# Analog_readout.net
KiCad netlist of a schematic drawn in Altium Designer
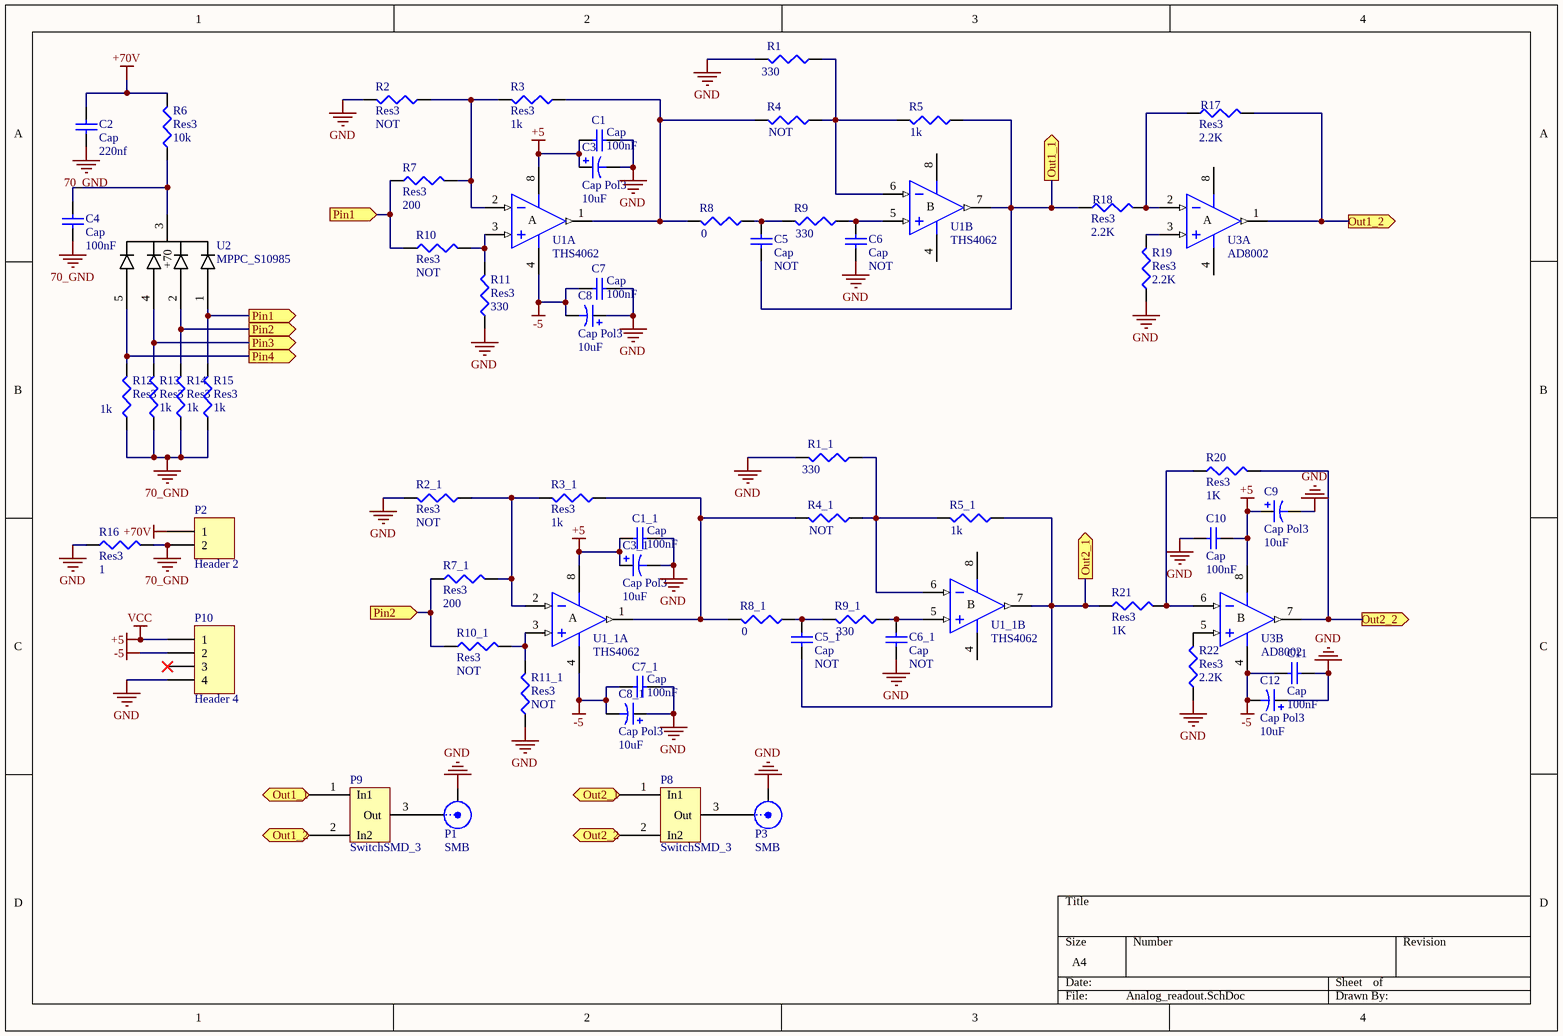
[diagram p0: Analog_readout.SchDoc]

(export (version "E")
  (design (tool "Eeschema 10.0.6"))
  (components
    (comp (ref "C1")
      (value "Cap")
      (footprint "6-0805_N")
      (description "Capacitor")
      (fields (field (name "ALTIUM_VALUE") "100nF") (field (name "PUBLISHER") "Altium Limited"))
      (libsource (lib "Miscellaneous Devices") (part "Cap"))
    )
    (comp (ref "C1_1")
      (value "Cap")
      (footprint "6-0805_N")
      (description "Capacitor")
      (fields (field (name "ALTIUM_VALUE") "100nF") (field (name "PUBLISHER") "Altium Limited"))
      (libsource (lib "Miscellaneous Devices") (part "Cap"))
    )
    (comp (ref "C2")
      (value "Cap")
      (footprint "6-0805_N")
      (description "Capacitor")
      (fields (field (name "ALTIUM_VALUE") "220nf") (field (name "PUBLISHER") "Altium Limited"))
      (libsource (lib "Miscellaneous Devices") (part "Cap"))
    )
    (comp (ref "C3")
      (value "Cap Pol3")
      (footprint "6-0805_N")
      (description "Polarized Capacitor (Surface Mount)")
      (fields (field (name "ALTIUM_VALUE") "10uF") (field (name "PUBLISHER") "Altium Limited"))
      (libsource (lib "Miscellaneous Devices") (part "Cap Pol3"))
    )
    (comp (ref "C3_1")
      (value "Cap Pol3")
      (footprint "6-0805_N")
      (description "Polarized Capacitor (Surface Mount)")
      (fields (field (name "ALTIUM_VALUE") "10uF") (field (name "PUBLISHER") "Altium Limited"))
      (libsource (lib "Miscellaneous Devices") (part "Cap Pol3"))
    )
    (comp (ref "C4")
      (value "Cap")
      (footprint "6-0805_N")
      (description "Capacitor")
      (fields (field (name "ALTIUM_VALUE") "100nF") (field (name "PUBLISHER") "Altium Limited"))
      (libsource (lib "Miscellaneous Devices") (part "Cap"))
    )
    (comp (ref "C5")
      (value "Cap")
      (footprint "6-0805_N")
      (description "Capacitor")
      (fields (field (name "ALTIUM_VALUE") "NOT") (field (name "PUBLISHER") "Altium Limited"))
      (libsource (lib "Miscellaneous Devices") (part "Cap"))
    )
    (comp (ref "C5_1")
      (value "Cap")
      (footprint "6-0805_N")
      (description "Capacitor")
      (fields (field (name "ALTIUM_VALUE") "NOT") (field (name "PUBLISHER") "Altium Limited"))
      (libsource (lib "Miscellaneous Devices") (part "Cap"))
    )
    (comp (ref "C6")
      (value "Cap")
      (footprint "6-0805_N")
      (description "Capacitor")
      (fields (field (name "ALTIUM_VALUE") "NOT") (field (name "PUBLISHER") "Altium Limited"))
      (libsource (lib "Miscellaneous Devices") (part "Cap"))
    )
    (comp (ref "C6_1")
      (value "Cap")
      (footprint "6-0805_N")
      (description "Capacitor")
      (fields (field (name "ALTIUM_VALUE") "NOT") (field (name "PUBLISHER") "Altium Limited"))
      (libsource (lib "Miscellaneous Devices") (part "Cap"))
    )
    (comp (ref "C7")
      (value "Cap")
      (footprint "6-0805_N")
      (description "Capacitor")
      (fields (field (name "ALTIUM_VALUE") "100nF") (field (name "PUBLISHER") "Altium Limited"))
      (libsource (lib "Miscellaneous Devices") (part "Cap"))
    )
    (comp (ref "C7_1")
      (value "Cap")
      (footprint "6-0805_N")
      (description "Capacitor")
      (fields (field (name "ALTIUM_VALUE") "100nF") (field (name "PUBLISHER") "Altium Limited"))
      (libsource (lib "Miscellaneous Devices") (part "Cap"))
    )
    (comp (ref "C8")
      (value "Cap Pol3")
      (footprint "6-0805_N")
      (description "Polarized Capacitor (Surface Mount)")
      (fields (field (name "ALTIUM_VALUE") "10uF") (field (name "PUBLISHER") "Altium Limited"))
      (libsource (lib "Miscellaneous Devices") (part "Cap Pol3"))
    )
    (comp (ref "C8_1")
      (value "Cap Pol3")
      (footprint "6-0805_N")
      (description "Polarized Capacitor (Surface Mount)")
      (fields (field (name "ALTIUM_VALUE") "10uF") (field (name "PUBLISHER") "Altium Limited"))
      (libsource (lib "Miscellaneous Devices") (part "Cap Pol3"))
    )
    (comp (ref "C9")
      (value "Cap Pol3")
      (footprint "6-0805_N")
      (description "Polarized Capacitor (Surface Mount)")
      (fields (field (name "ALTIUM_VALUE") "10uF") (field (name "PUBLISHER") "Altium Limited"))
      (libsource (lib "Miscellaneous Devices") (part "Cap Pol3"))
    )
    (comp (ref "C10")
      (value "Cap")
      (footprint "6-0805_N")
      (description "Capacitor")
      (fields (field (name "ALTIUM_VALUE") "100nF") (field (name "PUBLISHER") "Altium Limited"))
      (libsource (lib "Miscellaneous Devices") (part "Cap"))
    )
    (comp (ref "C11")
      (value "Cap")
      (footprint "6-0805_N")
      (description "Capacitor")
      (fields (field (name "ALTIUM_VALUE") "100nF") (field (name "PUBLISHER") "Altium Limited"))
      (libsource (lib "Miscellaneous Devices") (part "Cap"))
    )
    (comp (ref "C12")
      (value "Cap Pol3")
      (footprint "6-0805_N")
      (description "Polarized Capacitor (Surface Mount)")
      (fields (field (name "ALTIUM_VALUE") "10uF") (field (name "PUBLISHER") "Altium Limited"))
      (libsource (lib "Miscellaneous Devices") (part "Cap Pol3"))
    )
    (comp (ref "P1")
      (value "SMB")
      (footprint "SMB_V-RJ45")
      (description "SMB Straight Connector")
      (fields (field (name "PUBLISHER") "Altium Limited"))
      (libsource (lib "Miscellaneous Connectors") (part "SMB"))
    )
    (comp (ref "P2")
      (value "Header 2")
      (footprint "HDR1X2")
      (description "Header, 2-Pin")
      (fields (field (name "PUBLISHER") "Altium Limited"))
      (libsource (lib "Miscellaneous Connectors") (part "Header 2"))
    )
    (comp (ref "P3")
      (value "SMB")
      (footprint "SMB_V-RJ45")
      (description "SMB Straight Connector")
      (fields (field (name "PUBLISHER") "Altium Limited"))
      (libsource (lib "Miscellaneous Connectors") (part "SMB"))
    )
    (comp (ref "P8")
      (value "SwitchSMD_3")
      (footprint "SwitchSMD_0603")
      (libsource (lib "Int_Lib1") (part "SwitchSMD_3"))
    )
    (comp (ref "P9")
      (value "SwitchSMD_3")
      (footprint "SwitchSMD_0603")
      (libsource (lib "Int_Lib1") (part "SwitchSMD_3"))
    )
    (comp (ref "P10")
      (value "Header 4")
      (footprint "HDR1X4")
      (description "Header, 4-Pin")
      (fields (field (name "PUBLISHER") "Altium Limited"))
      (libsource (lib "Miscellaneous Connectors") (part "Header 4"))
    )
    (comp (ref "R1")
      (value "330")
      (footprint "6-0805_N")
      (description "Resistor")
      (fields (field (name "Comment") "Res3") (field (name "PUBLISHER") "Altium Limited"))
      (libsource (lib "Miscellaneous Devices") (part "Res3"))
    )
    (comp (ref "R1_1")
      (value "330")
      (footprint "6-0805_N")
      (description "Resistor")
      (fields (field (name "Comment") "Res3") (field (name "PUBLISHER") "Altium Limited"))
      (libsource (lib "Miscellaneous Devices") (part "Res3"))
    )
    (comp (ref "R2")
      (value "Res3")
      (footprint "6-0805_N")
      (description "Resistor")
      (fields (field (name "ALTIUM_VALUE") "NOT") (field (name "PUBLISHER") "Altium Limited"))
      (libsource (lib "Miscellaneous Devices") (part "Res3"))
    )
    (comp (ref "R2_1")
      (value "Res3")
      (footprint "6-0805_N")
      (description "Resistor")
      (fields (field (name "ALTIUM_VALUE") "NOT") (field (name "PUBLISHER") "Altium Limited"))
      (libsource (lib "Miscellaneous Devices") (part "Res3"))
    )
    (comp (ref "R3")
      (value "Res3")
      (footprint "6-0805_N")
      (description "Resistor")
      (fields (field (name "ALTIUM_VALUE") "1k") (field (name "PUBLISHER") "Altium Limited"))
      (libsource (lib "Miscellaneous Devices") (part "Res3"))
    )
    (comp (ref "R3_1")
      (value "Res3")
      (footprint "6-0805_N")
      (description "Resistor")
      (fields (field (name "ALTIUM_VALUE") "1k") (field (name "PUBLISHER") "Altium Limited"))
      (libsource (lib "Miscellaneous Devices") (part "Res3"))
    )
    (comp (ref "R4")
      (value "NOT")
      (footprint "6-0805_N")
      (description "Resistor")
      (fields (field (name "Comment") "Res3") (field (name "PUBLISHER") "Altium Limited"))
      (libsource (lib "Miscellaneous Devices") (part "Res3"))
    )
    (comp (ref "R4_1")
      (value "NOT")
      (footprint "6-0805_N")
      (description "Resistor")
      (fields (field (name "Comment") "Res3") (field (name "PUBLISHER") "Altium Limited"))
      (libsource (lib "Miscellaneous Devices") (part "Res3"))
    )
    (comp (ref "R5")
      (value "1k")
      (footprint "6-0805_N")
      (description "Resistor")
      (fields (field (name "Comment") "Res3") (field (name "PUBLISHER") "Altium Limited"))
      (libsource (lib "Miscellaneous Devices") (part "Res3"))
    )
    (comp (ref "R5_1")
      (value "1k")
      (footprint "6-0805_N")
      (description "Resistor")
      (fields (field (name "Comment") "Res3") (field (name "PUBLISHER") "Altium Limited"))
      (libsource (lib "Miscellaneous Devices") (part "Res3"))
    )
    (comp (ref "R6")
      (value "Res3")
      (footprint "6-0805_N")
      (description "Resistor")
      (fields (field (name "ALTIUM_VALUE") "10k") (field (name "PUBLISHER") "Altium Limited"))
      (libsource (lib "Miscellaneous Devices") (part "Res3"))
    )
    (comp (ref "R7")
      (value "Res3")
      (footprint "6-0805_N")
      (description "Resistor")
      (fields (field (name "ALTIUM_VALUE") "200") (field (name "PUBLISHER") "Altium Limited"))
      (libsource (lib "Miscellaneous Devices") (part "Res3"))
    )
    (comp (ref "R7_1")
      (value "Res3")
      (footprint "6-0805_N")
      (description "Resistor")
      (fields (field (name "ALTIUM_VALUE") "200") (field (name "PUBLISHER") "Altium Limited"))
      (libsource (lib "Miscellaneous Devices") (part "Res3"))
    )
    (comp (ref "R8")
      (value "0")
      (footprint "6-0805_N")
      (description "Resistor")
      (fields (field (name "Comment") "Res3") (field (name "PUBLISHER") "Altium Limited"))
      (libsource (lib "Miscellaneous Devices") (part "Res3"))
    )
    (comp (ref "R8_1")
      (value "0")
      (footprint "6-0805_N")
      (description "Resistor")
      (fields (field (name "Comment") "Res3") (field (name "PUBLISHER") "Altium Limited"))
      (libsource (lib "Miscellaneous Devices") (part "Res3"))
    )
    (comp (ref "R9")
      (value "330")
      (footprint "6-0805_N")
      (description "Resistor")
      (fields (field (name "Comment") "Res3") (field (name "PUBLISHER") "Altium Limited"))
      (libsource (lib "Miscellaneous Devices") (part "Res3"))
    )
    (comp (ref "R9_1")
      (value "330")
      (footprint "6-0805_N")
      (description "Resistor")
      (fields (field (name "Comment") "Res3") (field (name "PUBLISHER") "Altium Limited"))
      (libsource (lib "Miscellaneous Devices") (part "Res3"))
    )
    (comp (ref "R10")
      (value "Res3")
      (footprint "6-0805_N")
      (description "Resistor")
      (fields (field (name "ALTIUM_VALUE") "NOT") (field (name "PUBLISHER") "Altium Limited"))
      (libsource (lib "Miscellaneous Devices") (part "Res3"))
    )
    (comp (ref "R10_1")
      (value "Res3")
      (footprint "6-0805_N")
      (description "Resistor")
      (fields (field (name "ALTIUM_VALUE") "NOT") (field (name "PUBLISHER") "Altium Limited"))
      (libsource (lib "Miscellaneous Devices") (part "Res3"))
    )
    (comp (ref "R11")
      (value "Res3")
      (footprint "6-0805_N")
      (description "Resistor")
      (fields (field (name "ALTIUM_VALUE") "330") (field (name "PUBLISHER") "Altium Limited"))
      (libsource (lib "Miscellaneous Devices") (part "Res3"))
    )
    (comp (ref "R11_1")
      (value "Res3")
      (footprint "6-0805_N")
      (description "Resistor")
      (fields (field (name "ALTIUM_VALUE") "NOT") (field (name "PUBLISHER") "Altium Limited"))
      (libsource (lib "Miscellaneous Devices") (part "Res3"))
    )
    (comp (ref "R12")
      (value "Res3")
      (footprint "6-0805_N")
      (description "Resistor")
      (fields (field (name "ALTIUM_VALUE") "1k") (field (name "PUBLISHER") "Altium Limited"))
      (libsource (lib "Miscellaneous Devices") (part "Res3"))
    )
    (comp (ref "R13")
      (value "Res3")
      (footprint "6-0805_N")
      (description "Resistor")
      (fields (field (name "ALTIUM_VALUE") "1k") (field (name "PUBLISHER") "Altium Limited"))
      (libsource (lib "Miscellaneous Devices") (part "Res3"))
    )
    (comp (ref "R14")
      (value "Res3")
      (footprint "6-0805_N")
      (description "Resistor")
      (fields (field (name "ALTIUM_VALUE") "1k") (field (name "PUBLISHER") "Altium Limited"))
      (libsource (lib "Miscellaneous Devices") (part "Res3"))
    )
    (comp (ref "R15")
      (value "Res3")
      (footprint "6-0805_N")
      (description "Resistor")
      (fields (field (name "ALTIUM_VALUE") "1k") (field (name "PUBLISHER") "Altium Limited"))
      (libsource (lib "Miscellaneous Devices") (part "Res3"))
    )
    (comp (ref "R16")
      (value "Res3")
      (footprint "6-0805_N")
      (description "Resistor")
      (fields (field (name "ALTIUM_VALUE") "1") (field (name "PUBLISHER") "Altium Limited"))
      (libsource (lib "Miscellaneous Devices") (part "Res3"))
    )
    (comp (ref "R17")
      (value "Res3")
      (footprint "6-0805_N")
      (description "Resistor")
      (fields (field (name "ALTIUM_VALUE") "2.2K") (field (name "PUBLISHER") "Altium Limited"))
      (libsource (lib "Miscellaneous Devices") (part "Res3"))
    )
    (comp (ref "R18")
      (value "Res3")
      (footprint "6-0805_N")
      (description "Resistor")
      (fields (field (name "ALTIUM_VALUE") "2.2K") (field (name "PUBLISHER") "Altium Limited"))
      (libsource (lib "Miscellaneous Devices") (part "Res3"))
    )
    (comp (ref "R19")
      (value "Res3")
      (footprint "6-0805_N")
      (description "Resistor")
      (fields (field (name "ALTIUM_VALUE") "2.2K") (field (name "PUBLISHER") "Altium Limited"))
      (libsource (lib "Miscellaneous Devices") (part "Res3"))
    )
    (comp (ref "R20")
      (value "Res3")
      (footprint "6-0805_N")
      (description "Resistor")
      (fields (field (name "ALTIUM_VALUE") "1K") (field (name "PUBLISHER") "Altium Limited"))
      (libsource (lib "Miscellaneous Devices") (part "Res3"))
    )
    (comp (ref "R21")
      (value "Res3")
      (footprint "6-0805_N")
      (description "Resistor")
      (fields (field (name "ALTIUM_VALUE") "1K") (field (name "PUBLISHER") "Altium Limited"))
      (libsource (lib "Miscellaneous Devices") (part "Res3"))
    )
    (comp (ref "R22")
      (value "Res3")
      (footprint "6-0805_N")
      (description "Resistor")
      (fields (field (name "ALTIUM_VALUE") "2.2K") (field (name "PUBLISHER") "Altium Limited"))
      (libsource (lib "Miscellaneous Devices") (part "Res3"))
    )
    (comp (ref "U1")
      (value "THS4062")
      (footprint "SO-8_M")
      (description "Dual 600MHz, 50mW Current Feedback Amplifier")
      (fields (field (name "PUBLISHER") "Altium Limited"))
      (libsource (lib "AD Operational Amplifier") (part "AD8002AR"))
    )
    (comp (ref "U1_1")
      (value "THS4062")
      (footprint "SO-8_M")
      (description "Dual 600MHz, 50mW Current Feedback Amplifier")
      (fields (field (name "PUBLISHER") "Altium Limited"))
      (libsource (lib "AD Operational Amplifier") (part "AD8002AR"))
    )
    (comp (ref "U2")
      (value "MPPC_S10985")
      (footprint "S10985_HAM")
      (libsource (lib "Int_Lib1") (part "MPPC_S10985"))
    )
    (comp (ref "U3")
      (value "AD8002")
      (footprint "SO-8_M")
      (description "Dual 600MHz, 50mW Current Feedback Amplifier")
      (fields (field (name "PUBLISHER") "Altium Limited"))
      (libsource (lib "AD Operational Amplifier") (part "AD8002AR"))
    )
  )
  (nets
    (net (code "1") (name "+5") (class "Default")
      (node (ref "C1") (pin "2") (pinfunction "2_2") (pintype "passive"))
      (node (ref "C10") (pin "2") (pinfunction "2_2") (pintype "passive"))
      (node (ref "C1_1") (pin "2") (pinfunction "2_2") (pintype "passive"))
      (node (ref "C3") (pin "1") (pinfunction "1_1") (pintype "passive"))
      (node (ref "C3_1") (pin "1") (pinfunction "1_1") (pintype "passive"))
      (node (ref "C9") (pin "1") (pinfunction "1_1") (pintype "passive"))
      (node (ref "P10") (pin "1") (pinfunction "1_1") (pintype "passive"))
      (node (ref "U1") (pin "8") (pinfunction "V+_8") (pintype "power_in"))
      (node (ref "U1_1") (pin "8") (pinfunction "V+_8") (pintype "power_in"))
      (node (ref "U3") (pin "8") (pinfunction "V+_8") (pintype "power_in"))
    )
    (net (code "2") (name "+70V") (class "Default")
      (node (ref "C2") (pin "2") (pinfunction "2_2") (pintype "passive"))
      (node (ref "P2") (pin "1") (pinfunction "1_1") (pintype "passive"))
      (node (ref "R6") (pin "2") (pinfunction "2_2") (pintype "passive"))
    )
    (net (code "3") (name "-5") (class "Default")
      (node (ref "C11") (pin "1") (pinfunction "1_1") (pintype "passive"))
      (node (ref "C12") (pin "2") (pinfunction "2_2") (pintype "passive"))
      (node (ref "C7") (pin "2") (pinfunction "2_2") (pintype "passive"))
      (node (ref "C7_1") (pin "2") (pinfunction "2_2") (pintype "passive"))
      (node (ref "C8") (pin "2") (pinfunction "2_2") (pintype "passive"))
      (node (ref "C8_1") (pin "2") (pinfunction "2_2") (pintype "passive"))
      (node (ref "P10") (pin "2") (pinfunction "2_2") (pintype "passive"))
      (node (ref "U1") (pin "4") (pinfunction "V-_4") (pintype "power_in"))
      (node (ref "U1_1") (pin "4") (pinfunction "V-_4") (pintype "power_in"))
      (node (ref "U3") (pin "4") (pinfunction "V-_4") (pintype "power_in"))
    )
    (net (code "4") (name "/Out1_1") (class "Default")
      (node (ref "C5") (pin "2") (pinfunction "2_2") (pintype "passive"))
      (node (ref "P9") (pin "1") (pinfunction "In1_1") (pintype "passive"))
      (node (ref "R18") (pin "1") (pinfunction "1_1") (pintype "passive"))
      (node (ref "R5") (pin "1") (pinfunction "1_1") (pintype "passive"))
      (node (ref "U1") (pin "7") (pinfunction "OUT_7") (pintype "output"))
    )
    (net (code "5") (name "/Out1_2") (class "Default")
      (node (ref "P9") (pin "2") (pinfunction "In2_2") (pintype "passive"))
      (node (ref "R17") (pin "2") (pinfunction "2_2") (pintype "passive"))
      (node (ref "U3") (pin "1") (pinfunction "OUT_1") (pintype "output"))
    )
    (net (code "6") (name "/Out2_1") (class "Default")
      (node (ref "C5_1") (pin "2") (pinfunction "2_2") (pintype "passive"))
      (node (ref "P8") (pin "1") (pinfunction "In1_1") (pintype "passive"))
      (node (ref "R21") (pin "1") (pinfunction "1_1") (pintype "passive"))
      (node (ref "R5_1") (pin "1") (pinfunction "1_1") (pintype "passive"))
      (node (ref "U1_1") (pin "7") (pinfunction "OUT_7") (pintype "output"))
    )
    (net (code "7") (name "/Out2_2") (class "Default")
      (node (ref "P8") (pin "2") (pinfunction "In2_2") (pintype "passive"))
      (node (ref "R20") (pin "2") (pinfunction "2_2") (pintype "passive"))
      (node (ref "U3") (pin "7") (pinfunction "OUT_7") (pintype "output"))
    )
    (net (code "8") (name "/Pin1") (class "Default")
      (node (ref "R10") (pin "1") (pinfunction "1_1") (pintype "passive"))
      (node (ref "R15") (pin "2") (pinfunction "2_2") (pintype "passive"))
      (node (ref "R7") (pin "1") (pinfunction "1_1") (pintype "passive"))
      (node (ref "U2") (pin "1") (pinfunction "Pin1_1") (pintype "passive"))
    )
    (net (code "9") (name "/Pin2") (class "Default")
      (node (ref "R10_1") (pin "1") (pinfunction "1_1") (pintype "passive"))
      (node (ref "R14") (pin "2") (pinfunction "2_2") (pintype "passive"))
      (node (ref "R7_1") (pin "1") (pinfunction "1_1") (pintype "passive"))
      (node (ref "U2") (pin "2") (pinfunction "Pin2_2") (pintype "passive"))
    )
    (net (code "10") (name "/Pin3") (class "Default")
      (node (ref "R13") (pin "2") (pinfunction "2_2") (pintype "passive"))
      (node (ref "U2") (pin "4") (pinfunction "4_4") (pintype "passive"))
    )
    (net (code "11") (name "/Pin4") (class "Default")
      (node (ref "R12") (pin "2") (pinfunction "2_2") (pintype "passive"))
      (node (ref "U2") (pin "5") (pinfunction "5_5") (pintype "passive"))
    )
    (net (code "12") (name "70_GND") (class "Default")
      (node (ref "C2") (pin "1") (pinfunction "1_1") (pintype "passive"))
      (node (ref "C4") (pin "1") (pinfunction "1_1") (pintype "passive"))
      (node (ref "P2") (pin "2") (pinfunction "2_2") (pintype "passive"))
      (node (ref "R12") (pin "1") (pinfunction "1_1") (pintype "passive"))
      (node (ref "R13") (pin "1") (pinfunction "1_1") (pintype "passive"))
      (node (ref "R14") (pin "1") (pinfunction "1_1") (pintype "passive"))
      (node (ref "R15") (pin "1") (pinfunction "1_1") (pintype "passive"))
      (node (ref "R16") (pin "2") (pinfunction "2_2") (pintype "passive"))
    )
    (net (code "13") (name "GND") (class "Default")
      (node (ref "C1") (pin "1") (pinfunction "1_1") (pintype "passive"))
      (node (ref "C10") (pin "1") (pinfunction "1_1") (pintype "passive"))
      (node (ref "C11") (pin "2") (pinfunction "2_2") (pintype "passive"))
      (node (ref "C12") (pin "1") (pinfunction "1_1") (pintype "passive"))
      (node (ref "C1_1") (pin "1") (pinfunction "1_1") (pintype "passive"))
      (node (ref "C3") (pin "2") (pinfunction "2_2") (pintype "passive"))
      (node (ref "C3_1") (pin "2") (pinfunction "2_2") (pintype "passive"))
      (node (ref "C6") (pin "2") (pinfunction "2_2") (pintype "passive"))
      (node (ref "C6_1") (pin "2") (pinfunction "2_2") (pintype "passive"))
      (node (ref "C7") (pin "1") (pinfunction "1_1") (pintype "passive"))
      (node (ref "C7_1") (pin "1") (pinfunction "1_1") (pintype "passive"))
      (node (ref "C8") (pin "1") (pinfunction "1_1") (pintype "passive"))
      (node (ref "C8_1") (pin "1") (pinfunction "1_1") (pintype "passive"))
      (node (ref "C9") (pin "2") (pinfunction "2_2") (pintype "passive"))
      (node (ref "P1") (pin "2") (pinfunction "Y_2") (pintype "passive"))
      (node (ref "P10") (pin "4") (pinfunction "4_4") (pintype "passive"))
      (node (ref "P3") (pin "2") (pinfunction "Y_2") (pintype "passive"))
      (node (ref "R1") (pin "2") (pinfunction "2_2") (pintype "passive"))
      (node (ref "R11") (pin "1") (pinfunction "1_1") (pintype "passive"))
      (node (ref "R11_1") (pin "1") (pinfunction "1_1") (pintype "passive"))
      (node (ref "R16") (pin "1") (pinfunction "1_1") (pintype "passive"))
      (node (ref "R19") (pin "1") (pinfunction "1_1") (pintype "passive"))
      (node (ref "R1_1") (pin "2") (pinfunction "2_2") (pintype "passive"))
      (node (ref "R2") (pin "2") (pinfunction "2_2") (pintype "passive"))
      (node (ref "R22") (pin "1") (pinfunction "1_1") (pintype "passive"))
      (node (ref "R2_1") (pin "2") (pinfunction "2_2") (pintype "passive"))
    )
    (net (code "14") (name "Net-(C5-Pad1)") (class "Default")
      (node (ref "C5") (pin "1") (pinfunction "1_1") (pintype "passive"))
      (node (ref "R8") (pin "1") (pinfunction "1_1") (pintype "passive"))
      (node (ref "R9") (pin "2") (pinfunction "2_2") (pintype "passive"))
    )
    (net (code "15") (name "Net-(C5_1-Pad1)") (class "Default")
      (node (ref "C5_1") (pin "1") (pinfunction "1_1") (pintype "passive"))
      (node (ref "R8_1") (pin "1") (pinfunction "1_1") (pintype "passive"))
      (node (ref "R9_1") (pin "2") (pinfunction "2_2") (pintype "passive"))
    )
    (net (code "16") (name "Net-(P1-X)") (class "Default")
      (node (ref "P1") (pin "1") (pinfunction "X_1") (pintype "passive"))
      (node (ref "P9") (pin "3") (pinfunction "Out_3") (pintype "passive"))
    )
    (net (code "17") (name "Net-(P3-X)") (class "Default")
      (node (ref "P3") (pin "1") (pinfunction "X_1") (pintype "passive"))
      (node (ref "P8") (pin "3") (pinfunction "Out_3") (pintype "passive"))
    )
    (net (code "18") (name "Net-(U1A-IN+)") (class "Default")
      (node (ref "R10") (pin "2") (pinfunction "2_2") (pintype "passive"))
      (node (ref "R11") (pin "2") (pinfunction "2_2") (pintype "passive"))
      (node (ref "U1") (pin "3") (pinfunction "IN+_3") (pintype "input"))
    )
    (net (code "19") (name "Net-(U1A-IN-)") (class "Default")
      (node (ref "R2") (pin "1") (pinfunction "1_1") (pintype "passive"))
      (node (ref "R3") (pin "2") (pinfunction "2_2") (pintype "passive"))
      (node (ref "R7") (pin "2") (pinfunction "2_2") (pintype "passive"))
      (node (ref "U1") (pin "2") (pinfunction "IN-_2") (pintype "input"))
    )
    (net (code "20") (name "Net-(U1A-OUT)") (class "Default")
      (node (ref "R3") (pin "1") (pinfunction "1_1") (pintype "passive"))
      (node (ref "R4") (pin "2") (pinfunction "2_2") (pintype "passive"))
      (node (ref "R8") (pin "2") (pinfunction "2_2") (pintype "passive"))
      (node (ref "U1") (pin "1") (pinfunction "OUT_1") (pintype "output"))
    )
    (net (code "21") (name "Net-(U1B-IN+)") (class "Default")
      (node (ref "C6") (pin "1") (pinfunction "1_1") (pintype "passive"))
      (node (ref "R9") (pin "1") (pinfunction "1_1") (pintype "passive"))
      (node (ref "U1") (pin "5") (pinfunction "IN+_5") (pintype "input"))
    )
    (net (code "22") (name "Net-(U1B-IN-)") (class "Default")
      (node (ref "R1") (pin "1") (pinfunction "1_1") (pintype "passive"))
      (node (ref "R4") (pin "1") (pinfunction "1_1") (pintype "passive"))
      (node (ref "R5") (pin "2") (pinfunction "2_2") (pintype "passive"))
      (node (ref "U1") (pin "6") (pinfunction "IN-_6") (pintype "input"))
    )
    (net (code "23") (name "Net-(U1_1A-IN+)") (class "Default")
      (node (ref "R10_1") (pin "2") (pinfunction "2_2") (pintype "passive"))
      (node (ref "R11_1") (pin "2") (pinfunction "2_2") (pintype "passive"))
      (node (ref "U1_1") (pin "3") (pinfunction "IN+_3") (pintype "input"))
    )
    (net (code "24") (name "Net-(U1_1A-IN-)") (class "Default")
      (node (ref "R2_1") (pin "1") (pinfunction "1_1") (pintype "passive"))
      (node (ref "R3_1") (pin "2") (pinfunction "2_2") (pintype "passive"))
      (node (ref "R7_1") (pin "2") (pinfunction "2_2") (pintype "passive"))
      (node (ref "U1_1") (pin "2") (pinfunction "IN-_2") (pintype "input"))
    )
    (net (code "25") (name "Net-(U1_1A-OUT)") (class "Default")
      (node (ref "R3_1") (pin "1") (pinfunction "1_1") (pintype "passive"))
      (node (ref "R4_1") (pin "2") (pinfunction "2_2") (pintype "passive"))
      (node (ref "R8_1") (pin "2") (pinfunction "2_2") (pintype "passive"))
      (node (ref "U1_1") (pin "1") (pinfunction "OUT_1") (pintype "output"))
    )
    (net (code "26") (name "Net-(U1_1B-IN+)") (class "Default")
      (node (ref "C6_1") (pin "1") (pinfunction "1_1") (pintype "passive"))
      (node (ref "R9_1") (pin "1") (pinfunction "1_1") (pintype "passive"))
      (node (ref "U1_1") (pin "5") (pinfunction "IN+_5") (pintype "input"))
    )
    (net (code "27") (name "Net-(U1_1B-IN-)") (class "Default")
      (node (ref "R1_1") (pin "1") (pinfunction "1_1") (pintype "passive"))
      (node (ref "R4_1") (pin "1") (pinfunction "1_1") (pintype "passive"))
      (node (ref "R5_1") (pin "2") (pinfunction "2_2") (pintype "passive"))
      (node (ref "U1_1") (pin "6") (pinfunction "IN-_6") (pintype "input"))
    )
    (net (code "28") (name "Net-(U2-+70)") (class "Default")
      (node (ref "C4") (pin "2") (pinfunction "2_2") (pintype "passive"))
      (node (ref "R6") (pin "1") (pinfunction "1_1") (pintype "passive"))
      (node (ref "U2") (pin "3") (pinfunction "+70_3") (pintype "passive"))
    )
    (net (code "29") (name "Net-(U3A-IN+)") (class "Default")
      (node (ref "R19") (pin "2") (pinfunction "2_2") (pintype "passive"))
      (node (ref "U3") (pin "3") (pinfunction "IN+_3") (pintype "input"))
    )
    (net (code "30") (name "Net-(U3A-IN-)") (class "Default")
      (node (ref "R17") (pin "1") (pinfunction "1_1") (pintype "passive"))
      (node (ref "R18") (pin "2") (pinfunction "2_2") (pintype "passive"))
      (node (ref "U3") (pin "2") (pinfunction "IN-_2") (pintype "input"))
    )
    (net (code "31") (name "Net-(U3B-IN+)") (class "Default")
      (node (ref "R22") (pin "2") (pinfunction "2_2") (pintype "passive"))
      (node (ref "U3") (pin "5") (pinfunction "IN+_5") (pintype "input"))
    )
    (net (code "32") (name "Net-(U3B-IN-)") (class "Default")
      (node (ref "R20") (pin "1") (pinfunction "1_1") (pintype "passive"))
      (node (ref "R21") (pin "2") (pinfunction "2_2") (pintype "passive"))
      (node (ref "U3") (pin "6") (pinfunction "IN-_6") (pintype "input"))
    )
    (net (code "33") (name "unconnected-(P10-Pad3)") (class "Default")
      (node (ref "P10") (pin "3") (pinfunction "3_3") (pintype "passive+no_connect"))
    )
    (net (code "34") (name "unconnected-(U1B-V+-Pad8)") (class "Default")
      (node (ref "U1") (pin "8") (pinfunction "V+_8") (pintype "power_in"))
    )
    (net (code "35") (name "unconnected-(U1B-V--Pad4)") (class "Default")
      (node (ref "U1") (pin "4") (pinfunction "V-_4") (pintype "power_in"))
    )
    (net (code "36") (name "unconnected-(U1_1B-V+-Pad8)") (class "Default")
      (node (ref "U1_1") (pin "8") (pinfunction "V+_8") (pintype "power_in"))
    )
    (net (code "37") (name "unconnected-(U1_1B-V--Pad4)") (class "Default")
      (node (ref "U1_1") (pin "4") (pinfunction "V-_4") (pintype "power_in"))
    )
    (net (code "38") (name "unconnected-(U3A-V+-Pad8)") (class "Default")
      (node (ref "U3") (pin "8") (pinfunction "V+_8") (pintype "power_in"))
    )
    (net (code "39") (name "unconnected-(U3A-V--Pad4)") (class "Default")
      (node (ref "U3") (pin "4") (pinfunction "V-_4") (pintype "power_in"))
    )
  )
)
